# On_Axis_Encoder.net
KiCad netlist of a schematic drawn in EAGLE
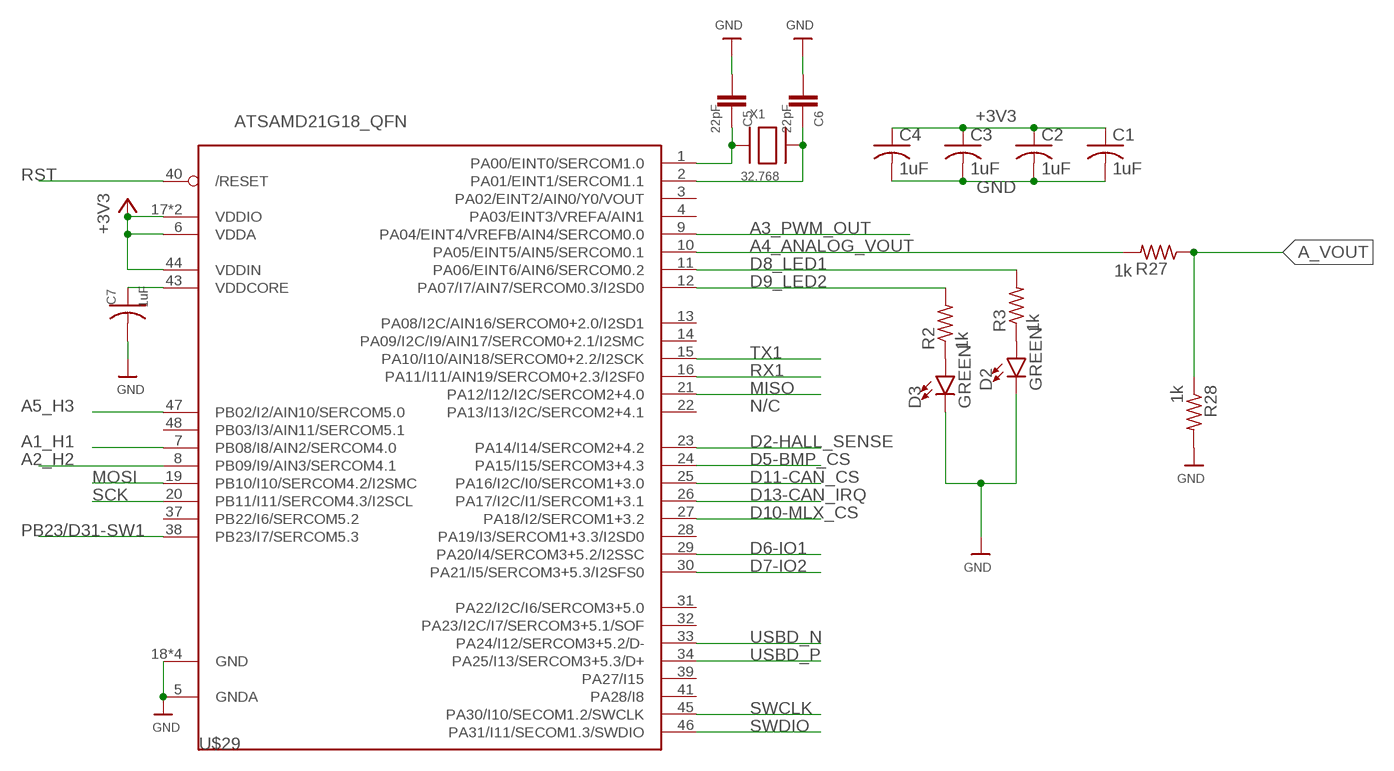
[diagram p0: schematic, sheet 1]
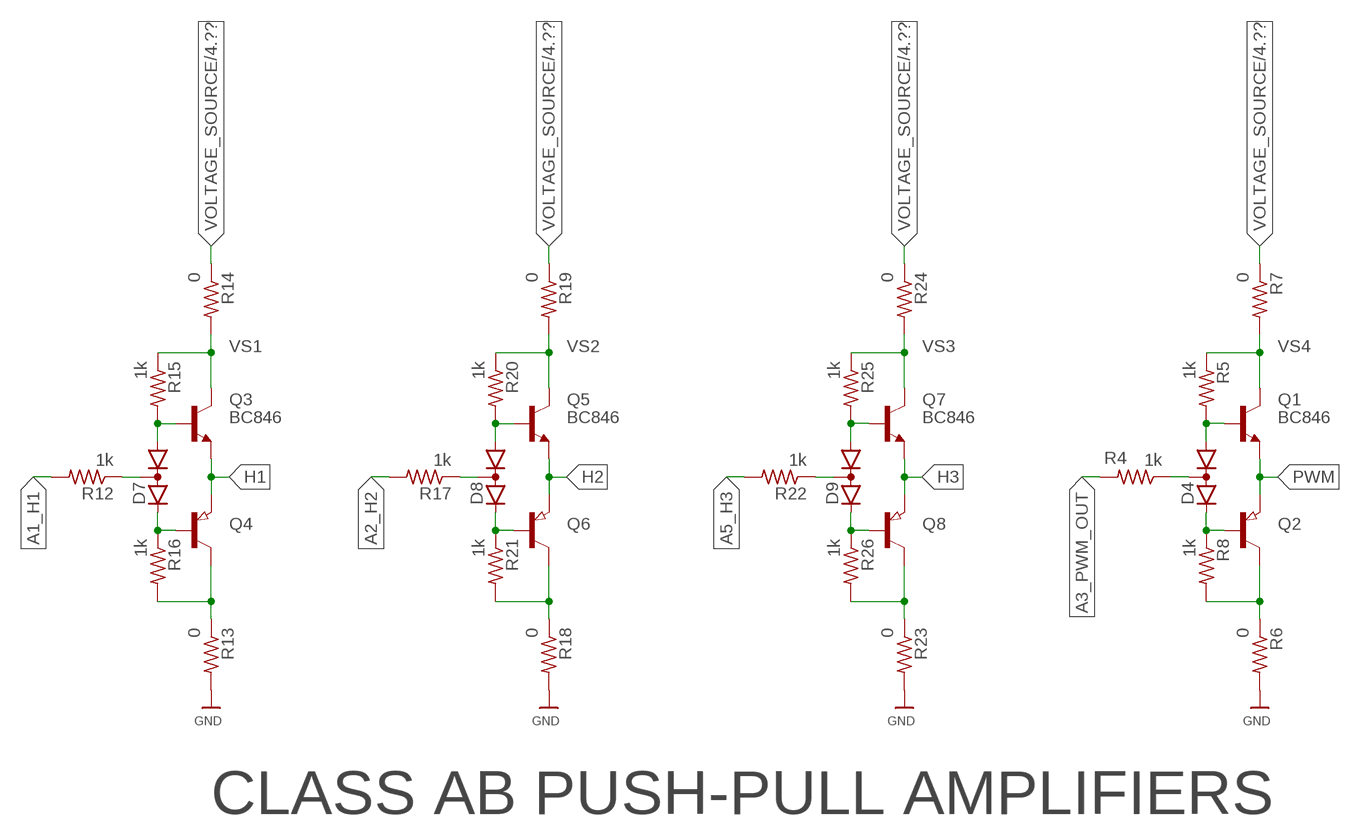
[diagram p1: schematic, sheet 2]
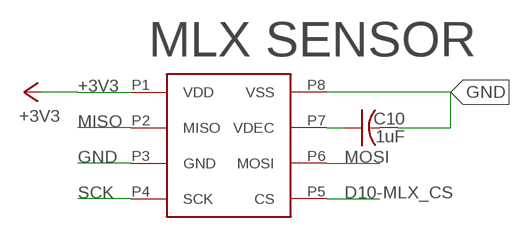
[diagram p2: schematic, sheet 3]
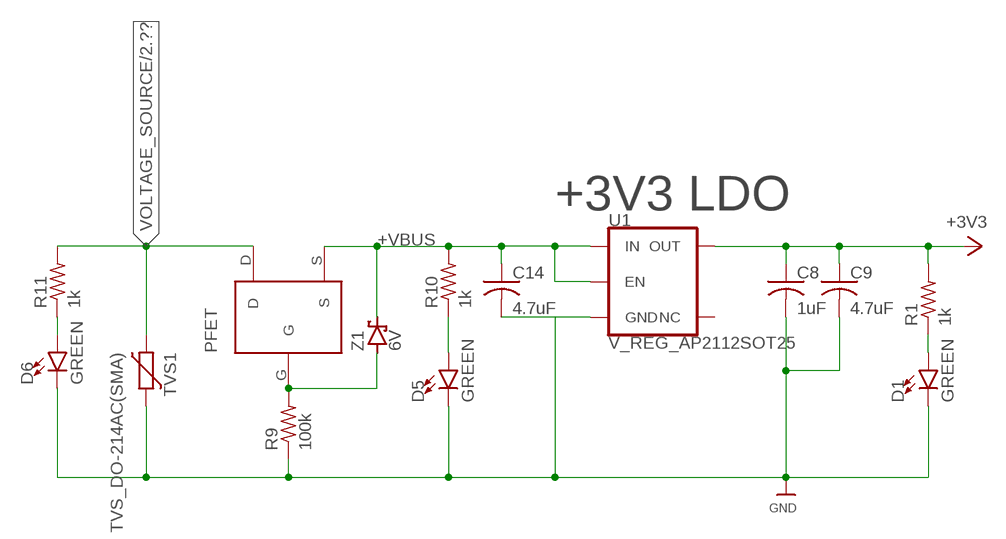
[diagram p3: schematic, sheet 4]
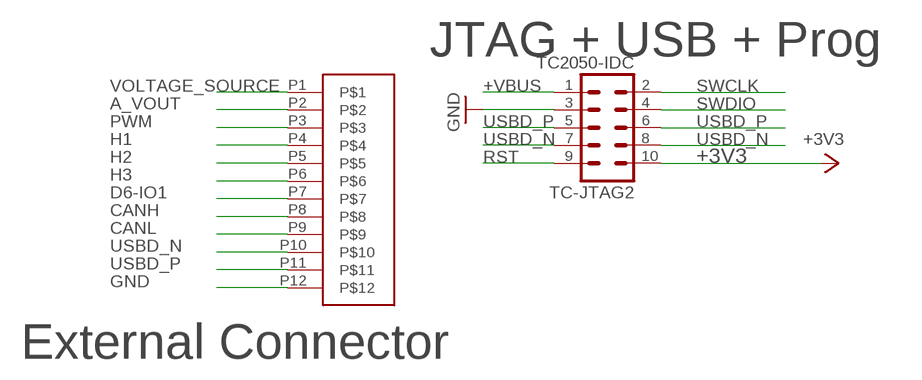
[diagram p4: schematic, sheet 5]
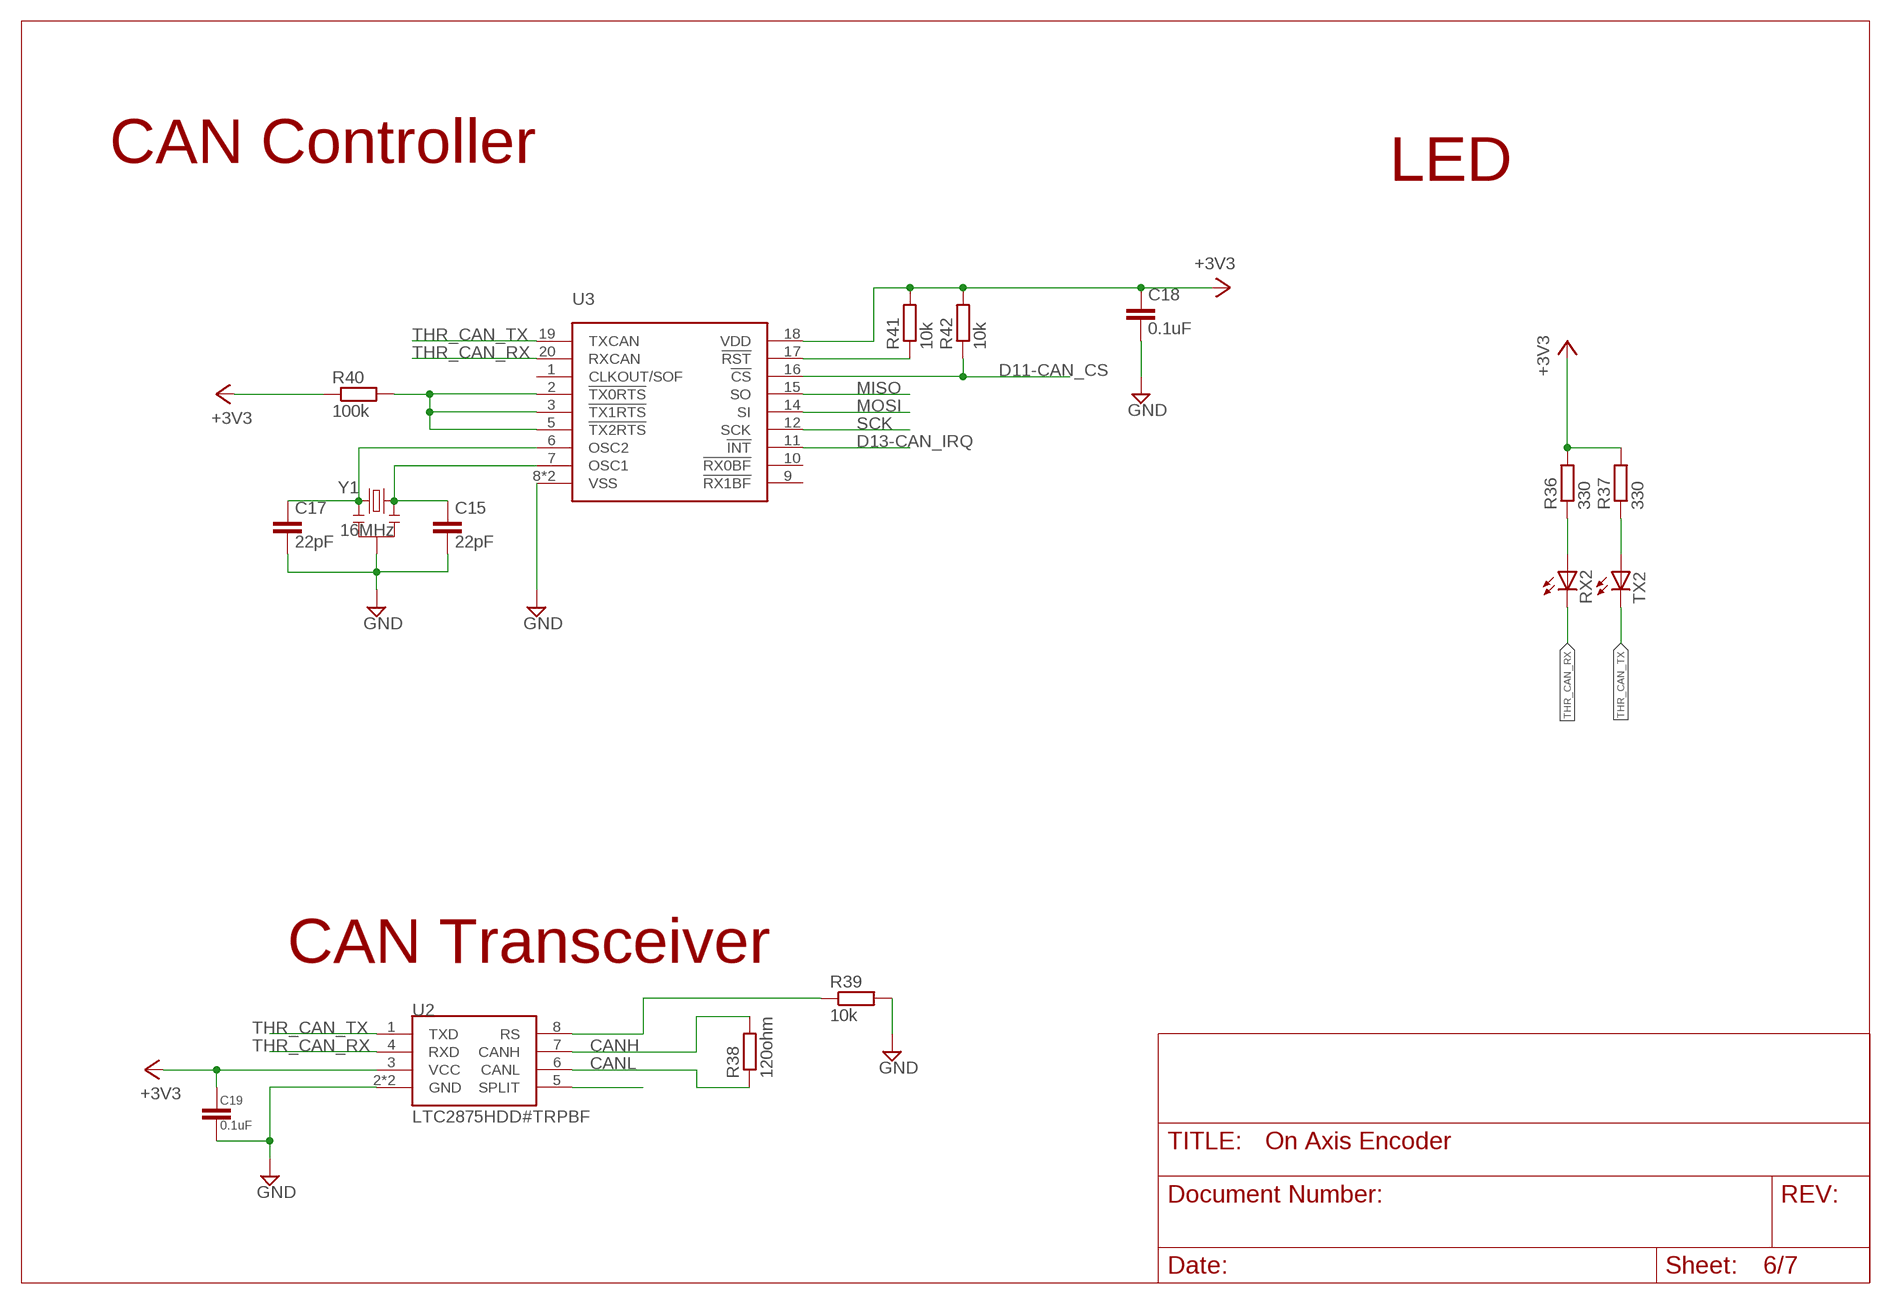
[diagram p5: schematic, sheet 6]

(export (version "E")
  (design (tool "Eeschema 10.0.6"))
  (components
    (comp (ref "D4")
      (value "DIODE_AC-AC__")
      (footprint "eagle-import:SOT23C")
      (libsource (lib "eagle-import") (part "DIODE_AC-AC__"))
    )
    (comp (ref "D7")
      (value "DIODE_AC-AC__")
      (footprint "eagle-import:SOT23C")
      (libsource (lib "eagle-import") (part "DIODE_AC-AC__"))
    )
    (comp (ref "D8")
      (value "DIODE_AC-AC__")
      (footprint "eagle-import:SOT23C")
      (libsource (lib "eagle-import") (part "DIODE_AC-AC__"))
    )
    (comp (ref "D9")
      (value "DIODE_AC-AC__")
      (footprint "eagle-import:SOT23C")
      (libsource (lib "eagle-import") (part "DIODE_AC-AC__"))
    )
    (comp (ref "Q1")
      (value "BC846")
      (footprint "eagle-import:SOT23")
      (libsource (lib "eagle-import") (part "BC846"))
    )
    (comp (ref "Q2")
      (value "PNP-TRANSISTOR_SOT23")
      (footprint "eagle-import:SOT23")
      (libsource (lib "eagle-import") (part "PNP-TRANSISTOR_SOT23"))
    )
    (comp (ref "Q3")
      (value "BC846")
      (footprint "eagle-import:SOT23")
      (libsource (lib "eagle-import") (part "BC846"))
    )
    (comp (ref "Q4")
      (value "PNP-TRANSISTOR_SOT23")
      (footprint "eagle-import:SOT23")
      (libsource (lib "eagle-import") (part "PNP-TRANSISTOR_SOT23"))
    )
    (comp (ref "Q5")
      (value "BC846")
      (footprint "eagle-import:SOT23")
      (libsource (lib "eagle-import") (part "BC846"))
    )
    (comp (ref "Q6")
      (value "PNP-TRANSISTOR_SOT23")
      (footprint "eagle-import:SOT23")
      (libsource (lib "eagle-import") (part "PNP-TRANSISTOR_SOT23"))
    )
    (comp (ref "Q7")
      (value "BC846")
      (footprint "eagle-import:SOT23")
      (libsource (lib "eagle-import") (part "BC846"))
    )
    (comp (ref "Q8")
      (value "PNP-TRANSISTOR_SOT23")
      (footprint "eagle-import:SOT23")
      (libsource (lib "eagle-import") (part "PNP-TRANSISTOR_SOT23"))
    )
    (comp (ref "R4")
      (value "1k")
      (footprint "eagle-import:R0603")
      (libsource (lib "eagle-import") (part "R-US_R0603"))
    )
    (comp (ref "R5")
      (value "1k")
      (footprint "eagle-import:R0603")
      (libsource (lib "eagle-import") (part "R-US_R0603"))
    )
    (comp (ref "R6")
      (value "0")
      (footprint "eagle-import:R0603")
      (libsource (lib "eagle-import") (part "R-US_R0603"))
    )
    (comp (ref "R7")
      (value "0")
      (footprint "eagle-import:R0603")
      (libsource (lib "eagle-import") (part "R-US_R0603"))
    )
    (comp (ref "R8")
      (value "1k")
      (footprint "eagle-import:R0603")
      (libsource (lib "eagle-import") (part "R-US_R0603"))
    )
    (comp (ref "R12")
      (value "1k")
      (footprint "eagle-import:R0603")
      (libsource (lib "eagle-import") (part "R-US_R0603"))
    )
    (comp (ref "R13")
      (value "0")
      (footprint "eagle-import:R0603")
      (libsource (lib "eagle-import") (part "R-US_R0603"))
    )
    (comp (ref "R14")
      (value "0")
      (footprint "eagle-import:R0603")
      (libsource (lib "eagle-import") (part "R-US_R0603"))
    )
    (comp (ref "R15")
      (value "1k")
      (footprint "eagle-import:R0603")
      (libsource (lib "eagle-import") (part "R-US_R0603"))
    )
    (comp (ref "R16")
      (value "1k")
      (footprint "eagle-import:R0603")
      (libsource (lib "eagle-import") (part "R-US_R0603"))
    )
    (comp (ref "R17")
      (value "1k")
      (footprint "eagle-import:R0603")
      (libsource (lib "eagle-import") (part "R-US_R0603"))
    )
    (comp (ref "R18")
      (value "0")
      (footprint "eagle-import:R0603")
      (libsource (lib "eagle-import") (part "R-US_R0603"))
    )
    (comp (ref "R19")
      (value "0")
      (footprint "eagle-import:R0603")
      (libsource (lib "eagle-import") (part "R-US_R0603"))
    )
    (comp (ref "R20")
      (value "1k")
      (footprint "eagle-import:R0603")
      (libsource (lib "eagle-import") (part "R-US_R0603"))
    )
    (comp (ref "R21")
      (value "1k")
      (footprint "eagle-import:R0603")
      (libsource (lib "eagle-import") (part "R-US_R0603"))
    )
    (comp (ref "R22")
      (value "1k")
      (footprint "eagle-import:R0603")
      (libsource (lib "eagle-import") (part "R-US_R0603"))
    )
    (comp (ref "R23")
      (value "0")
      (footprint "eagle-import:R0603")
      (libsource (lib "eagle-import") (part "R-US_R0603"))
    )
    (comp (ref "R24")
      (value "0")
      (footprint "eagle-import:R0603")
      (libsource (lib "eagle-import") (part "R-US_R0603"))
    )
    (comp (ref "R25")
      (value "1k")
      (footprint "eagle-import:R0603")
      (libsource (lib "eagle-import") (part "R-US_R0603"))
    )
    (comp (ref "R26")
      (value "1k")
      (footprint "eagle-import:R0603")
      (libsource (lib "eagle-import") (part "R-US_R0603"))
    )
    (comp (ref "C10")
      (value "1uF")
      (footprint "eagle-import:C0603")
      (libsource (lib "eagle-import") (part "C-USC0603"))
    )
    (comp (ref "U$4")
      (value "MLX90363-SOIC8")
      (footprint "eagle-import:SOIC-8")
      (libsource (lib "eagle-import") (part "MLX90363-SOIC8"))
    )
    (comp (ref "C15")
      (value "22pF")
      (footprint "eagle-import:C-0603")
      (libsource (lib "eagle-import") (part "C0603"))
    )
    (comp (ref "C17")
      (value "22pF")
      (footprint "eagle-import:C-0603")
      (libsource (lib "eagle-import") (part "C0603"))
    )
    (comp (ref "C18")
      (value "0.1uF")
      (footprint "eagle-import:C-0603")
      (libsource (lib "eagle-import") (part "C0603"))
    )
    (comp (ref "C19")
      (value "0.1uF")
      (footprint "eagle-import:C-0603")
      (libsource (lib "eagle-import") (part "C0603"))
    )
    (comp (ref "R36")
      (value "330")
      (footprint "eagle-import:R-0603")
      (libsource (lib "eagle-import") (part "R0603"))
    )
    (comp (ref "R37")
      (value "330")
      (footprint "eagle-import:R-0603")
      (libsource (lib "eagle-import") (part "R0603"))
    )
    (comp (ref "R38")
      (value "120ohm")
      (footprint "eagle-import:R-0603")
      (libsource (lib "eagle-import") (part "R0603"))
    )
    (comp (ref "R39")
      (value "10k")
      (footprint "eagle-import:R-0603")
      (libsource (lib "eagle-import") (part "R0603"))
    )
    (comp (ref "R40")
      (value "100k")
      (footprint "eagle-import:R-0603")
      (libsource (lib "eagle-import") (part "R0603"))
    )
    (comp (ref "R41")
      (value "10k")
      (footprint "eagle-import:R-0603")
      (libsource (lib "eagle-import") (part "R0603"))
    )
    (comp (ref "R42")
      (value "10k")
      (footprint "eagle-import:R-0603")
      (libsource (lib "eagle-import") (part "R0603"))
    )
    (comp (ref "RX2")
      (value "LEDCHIPLED_0805")
      (footprint "eagle-import:CHIPLED_0805")
      (libsource (lib "eagle-import") (part "LEDCHIPLED_0805"))
    )
    (comp (ref "TX2")
      (value "LEDCHIPLED_0805")
      (footprint "eagle-import:CHIPLED_0805")
      (libsource (lib "eagle-import") (part "LEDCHIPLED_0805"))
    )
    (comp (ref "U2")
      (value "LTC2875HDD#TRPBF")
      (footprint "eagle-import:SON50P300X300X80-9T165X238N")
      (libsource (lib "eagle-import") (part "LTC2875-8-DFN"))
    )
    (comp (ref "U3")
      (value "MCP2515-E/ML")
      (footprint "eagle-import:QFN50P400X400X100-21T270N")
      (libsource (lib "eagle-import") (part "MCP2515QFN-20"))
    )
    (comp (ref "Y1")
      (value "16MHz")
      (footprint "eagle-import:RESONATOR-SMD")
      (libsource (lib "eagle-import") (part "RESONATORSMD"))
    )
    (comp (ref "C1")
      (value "1uF")
      (footprint "eagle-import:C0603")
      (libsource (lib "eagle-import") (part "C-USC0603"))
    )
    (comp (ref "C2")
      (value "1uF")
      (footprint "eagle-import:C0603")
      (libsource (lib "eagle-import") (part "C-USC0603"))
    )
    (comp (ref "C3")
      (value "1uF")
      (footprint "eagle-import:C0603")
      (libsource (lib "eagle-import") (part "C-USC0603"))
    )
    (comp (ref "C4")
      (value "1uF")
      (footprint "eagle-import:C0603")
      (libsource (lib "eagle-import") (part "C-USC0603"))
    )
    (comp (ref "C5")
      (value "22pF")
      (footprint "eagle-import:C-0402")
      (libsource (lib "eagle-import") (part "C0402"))
    )
    (comp (ref "C6")
      (value "22pF")
      (footprint "eagle-import:C-0402")
      (libsource (lib "eagle-import") (part "C0402"))
    )
    (comp (ref "C7")
      (value "1uF")
      (footprint "eagle-import:C0603")
      (libsource (lib "eagle-import") (part "C-USC0603"))
    )
    (comp (ref "D2")
      (value "GREEN")
      (footprint "eagle-import:LED-0603")
      (libsource (lib "eagle-import") (part "LED-RED0603"))
    )
    (comp (ref "D3")
      (value "GREEN")
      (footprint "eagle-import:LED-0603")
      (libsource (lib "eagle-import") (part "LED-RED0603"))
    )
    (comp (ref "R2")
      (value "1k")
      (footprint "eagle-import:R0603")
      (libsource (lib "eagle-import") (part "R-US_R0603"))
    )
    (comp (ref "R3")
      (value "1k")
      (footprint "eagle-import:R0603")
      (libsource (lib "eagle-import") (part "R-US_R0603"))
    )
    (comp (ref "R27")
      (value "1k")
      (footprint "eagle-import:R0603")
      (libsource (lib "eagle-import") (part "R-US_R0603"))
    )
    (comp (ref "R28")
      (value "1k")
      (footprint "eagle-import:R0603")
      (libsource (lib "eagle-import") (part "R-US_R0603"))
    )
    (comp (ref "U$29")
      (value "ATSAMD21G18_QFN")
      (footprint "eagle-import:MICROBUILDER_TQFN48_7MM")
      (libsource (lib "eagle-import") (part "ATSAMD21J_QFN"))
    )
    (comp (ref "X1")
      (value "32.768")
      (footprint "eagle-import:XTAL3215")
      (libsource (lib "eagle-import") (part "XTAL-3.2X1.5"))
    )
    (comp (ref "TC-JTAG2")
      (value "TC2050-IDC")
      (footprint "eagle-import:TC2050-IDC")
      (libsource (lib "eagle-import") (part "TC2050-IDC"))
    )
    (comp (ref "U$9")
      (value "BM12B-ZESS-TBT")
      (footprint "eagle-import:JST-BM12B-ZESS-TBT")
      (libsource (lib "eagle-import") (part "BM12B-ZESS-TBT"))
    )
    (comp (ref "C8")
      (value "1uF")
      (footprint "eagle-import:C0603")
      (libsource (lib "eagle-import") (part "C-USC0603"))
    )
    (comp (ref "C9")
      (value "4.7uF")
      (footprint "eagle-import:C0603")
      (libsource (lib "eagle-import") (part "C-USC0603"))
    )
    (comp (ref "C14")
      (value "4.7uF")
      (footprint "eagle-import:C0603")
      (libsource (lib "eagle-import") (part "C-USC0603"))
    )
    (comp (ref "D1")
      (value "GREEN")
      (footprint "eagle-import:LED-0603")
      (libsource (lib "eagle-import") (part "LED-RED0603"))
    )
    (comp (ref "D5")
      (value "GREEN")
      (footprint "eagle-import:LED-0603")
      (libsource (lib "eagle-import") (part "LED-RED0603"))
    )
    (comp (ref "D6")
      (value "GREEN")
      (footprint "eagle-import:LED-0603")
      (libsource (lib "eagle-import") (part "LED-RED0603"))
    )
    (comp (ref "PFET1")
      (value "PFET")
      (footprint "eagle-import:SOT323-3_NFET")
      (libsource (lib "eagle-import") (part "NFET"))
    )
    (comp (ref "R1")
      (value "1k")
      (footprint "eagle-import:R0603")
      (libsource (lib "eagle-import") (part "R-US_R0603"))
    )
    (comp (ref "R9")
      (value "100k")
      (footprint "eagle-import:R0603")
      (libsource (lib "eagle-import") (part "R-US_R0603"))
    )
    (comp (ref "R10")
      (value "1k")
      (footprint "eagle-import:R0603")
      (libsource (lib "eagle-import") (part "R-US_R0603"))
    )
    (comp (ref "R11")
      (value "1k")
      (footprint "eagle-import:R0603")
      (libsource (lib "eagle-import") (part "R-US_R0603"))
    )
    (comp (ref "TVS1")
      (value "TVS_DO-214AC(SMA)")
      (footprint "eagle-import:DIOM5226X290N")
      (libsource (lib "eagle-import") (part "TVSDO-214AC(SMA)_"))
    )
    (comp (ref "U1")
      (value "V_REG_AP2112SOT25")
      (footprint "eagle-import:SOT95P285X140-5N")
      (libsource (lib "eagle-import") (part "V_REG_AP2112SOT25"))
    )
    (comp (ref "Z1")
      (value "6V")
      (footprint "eagle-import:SOT23")
      (libsource (lib "eagle-import") (part "BAS40"))
    )
  )
  (nets
    (net (code "1") (name "+3V3") (class "Default")
      (node (ref "C1") (pin "1") (pinfunction "1_1") (pintype "passive"))
      (node (ref "C18") (pin "P$1") (pinfunction "1_P$1") (pintype "passive"))
      (node (ref "C19") (pin "P$1") (pinfunction "1_P$1") (pintype "passive"))
      (node (ref "C2") (pin "1") (pinfunction "1_1") (pintype "passive"))
      (node (ref "C3") (pin "1") (pinfunction "1_1") (pintype "passive"))
      (node (ref "C4") (pin "1") (pinfunction "1_1") (pintype "passive"))
      (node (ref "C8") (pin "1") (pinfunction "1_1") (pintype "passive"))
      (node (ref "C9") (pin "1") (pinfunction "1_1") (pintype "passive"))
      (node (ref "R1") (pin "2") (pinfunction "2_2") (pintype "passive"))
      (node (ref "R36") (pin "P$2") (pinfunction "2_P$2") (pintype "passive"))
      (node (ref "R37") (pin "P$2") (pinfunction "2_P$2") (pintype "passive"))
      (node (ref "R40") (pin "P$1") (pinfunction "1_P$1") (pintype "passive"))
      (node (ref "R41") (pin "P$2") (pinfunction "2_P$2") (pintype "passive"))
      (node (ref "R42") (pin "P$2") (pinfunction "2_P$2") (pintype "passive"))
      (node (ref "TC-JTAG2") (pin "10") (pinfunction "10_10") (pintype "passive"))
      (node (ref "U$29") (pin "17") (pinfunction "VDDIO_17") (pintype "power_in"))
      (node (ref "U$29") (pin "36") (pinfunction "VDDIO_36") (pintype "power_in"))
      (node (ref "U$29") (pin "44") (pinfunction "VDDIN_44") (pintype "power_in"))
      (node (ref "U$29") (pin "6") (pinfunction "VDDA_6") (pintype "power_in"))
      (node (ref "U$4") (pin "P1") (pinfunction "VDD_P1") (pintype "bidirectional"))
      (node (ref "U1") (pin "5") (pinfunction "OUT_5") (pintype "passive"))
      (node (ref "U2") (pin "3") (pinfunction "VCC_3") (pintype "bidirectional"))
      (node (ref "U3") (pin "18") (pinfunction "VDD_18") (pintype "bidirectional"))
    )
    (net (code "2") (name "+VBUS") (class "Default")
      (node (ref "C14") (pin "1") (pinfunction "1_1") (pintype "passive"))
      (node (ref "PFET1") (pin "S") (pinfunction "S_S") (pintype "bidirectional"))
      (node (ref "R10") (pin "2") (pinfunction "2_2") (pintype "passive"))
      (node (ref "TC-JTAG2") (pin "1") (pinfunction "1_1") (pintype "passive"))
      (node (ref "U1") (pin "1") (pinfunction "IN_1") (pintype "input"))
      (node (ref "U1") (pin "3") (pinfunction "EN_3") (pintype "input"))
      (node (ref "Z1") (pin "3") (pinfunction "C_3") (pintype "passive"))
    )
    (net (code "3") (name "A1_H1") (class "Default")
      (node (ref "R12") (pin "2") (pinfunction "2_2") (pintype "passive"))
      (node (ref "U$29") (pin "7") (pinfunction "PB08/I8/AIN2/SERCOM4.0_7") (pintype "bidirectional"))
    )
    (net (code "4") (name "A2_H2") (class "Default")
      (node (ref "R17") (pin "2") (pinfunction "2_2") (pintype "passive"))
      (node (ref "U$29") (pin "8") (pinfunction "PB09/I9/AIN3/SERCOM4.1_8") (pintype "bidirectional"))
    )
    (net (code "5") (name "A3_PWM_OUT") (class "Default")
      (node (ref "R4") (pin "2") (pinfunction "2_2") (pintype "passive"))
      (node (ref "U$29") (pin "9") (pinfunction "PA04/EINT4/VREFB/AIN4/SERCOM0.0_9") (pintype "bidirectional"))
    )
    (net (code "6") (name "A4_ANALOG_VOUT") (class "Default")
      (node (ref "R27") (pin "2") (pinfunction "2_2") (pintype "passive"))
      (node (ref "U$29") (pin "10") (pinfunction "PA05/EINT5/AIN5/SERCOM0.1_10") (pintype "bidirectional"))
    )
    (net (code "7") (name "A5_H3") (class "Default")
      (node (ref "R22") (pin "2") (pinfunction "2_2") (pintype "passive"))
      (node (ref "U$29") (pin "47") (pinfunction "PB02/I2/AIN10/SERCOM5.0_47") (pintype "bidirectional"))
    )
    (net (code "8") (name "A_VOUT") (class "Default")
      (node (ref "R27") (pin "1") (pinfunction "1_1") (pintype "passive"))
      (node (ref "R28") (pin "1") (pinfunction "1_1") (pintype "passive"))
      (node (ref "U$9") (pin "P2") (pinfunction "P$2_P2") (pintype "bidirectional"))
    )
    (net (code "9") (name "CANH") (class "Default")
      (node (ref "R38") (pin "P$2") (pinfunction "2_P$2") (pintype "passive"))
      (node (ref "U$9") (pin "P8") (pinfunction "P$8_P8") (pintype "bidirectional"))
      (node (ref "U2") (pin "7") (pinfunction "CANH_7") (pintype "bidirectional"))
    )
    (net (code "10") (name "CANL") (class "Default")
      (node (ref "R38") (pin "P$1") (pinfunction "1_P$1") (pintype "passive"))
      (node (ref "U$9") (pin "P9") (pinfunction "P$9_P9") (pintype "bidirectional"))
      (node (ref "U2") (pin "6") (pinfunction "CANL_6") (pintype "bidirectional"))
    )
    (net (code "11") (name "D2-HALL_SENSE") (class "Default")
      (node (ref "U$29") (pin "23") (pinfunction "PA14/I14/SERCOM2+4.2_23") (pintype "bidirectional"))
    )
    (net (code "12") (name "D5-BMP_CS") (class "Default")
      (node (ref "U$29") (pin "24") (pinfunction "PA15/I15/SERCOM3+4.3_24") (pintype "bidirectional"))
    )
    (net (code "13") (name "D6-IO1") (class "Default")
      (node (ref "U$29") (pin "29") (pinfunction "PA20/I4/SERCOM3+5.2/I2SSC_29") (pintype "bidirectional"))
      (node (ref "U$9") (pin "P7") (pinfunction "P$7_P7") (pintype "bidirectional"))
    )
    (net (code "14") (name "D7-IO2") (class "Default")
      (node (ref "U$29") (pin "30") (pinfunction "PA21/I5/SERCOM3+5.3/I2SFS0_30") (pintype "bidirectional"))
    )
    (net (code "15") (name "D8_LED1") (class "Default")
      (node (ref "R3") (pin "2") (pinfunction "2_2") (pintype "passive"))
      (node (ref "U$29") (pin "11") (pinfunction "PA06/EINT6/AIN6/SERCOM0.2_11") (pintype "bidirectional"))
    )
    (net (code "16") (name "D9_LED2") (class "Default")
      (node (ref "R2") (pin "2") (pinfunction "2_2") (pintype "passive"))
      (node (ref "U$29") (pin "12") (pinfunction "PA07/I7/AIN7/SERCOM0.3/I2SD0_12") (pintype "bidirectional"))
    )
    (net (code "17") (name "D10-MLX_CS") (class "Default")
      (node (ref "U$29") (pin "27") (pinfunction "PA18/I2/SERCOM1+3.2_27") (pintype "bidirectional"))
      (node (ref "U$4") (pin "P5") (pinfunction "CS_P5") (pintype "bidirectional"))
    )
    (net (code "18") (name "D11-CAN_CS") (class "Default")
      (node (ref "R42") (pin "P$1") (pinfunction "1_P$1") (pintype "passive"))
      (node (ref "U$29") (pin "25") (pinfunction "PA16/I2C/I0/SERCOM1+3.0_25") (pintype "bidirectional"))
      (node (ref "U3") (pin "16") (pinfunction "~{CS}_16") (pintype "bidirectional"))
    )
    (net (code "19") (name "D13-CAN_IRQ") (class "Default")
      (node (ref "U$29") (pin "26") (pinfunction "PA17/I2C/I1/SERCOM1+3.1_26") (pintype "bidirectional"))
      (node (ref "U3") (pin "11") (pinfunction "~{INT}_11") (pintype "bidirectional"))
    )
    (net (code "20") (name "GND") (class "Default")
      (node (ref "C1") (pin "2") (pinfunction "2_2") (pintype "passive"))
      (node (ref "C10") (pin "2") (pinfunction "2_2") (pintype "passive"))
      (node (ref "C14") (pin "2") (pinfunction "2_2") (pintype "passive"))
      (node (ref "C15") (pin "P$2") (pinfunction "2_P$2") (pintype "passive"))
      (node (ref "C17") (pin "P$2") (pinfunction "2_P$2") (pintype "passive"))
      (node (ref "C18") (pin "P$2") (pinfunction "2_P$2") (pintype "passive"))
      (node (ref "C19") (pin "P$2") (pinfunction "2_P$2") (pintype "passive"))
      (node (ref "C2") (pin "2") (pinfunction "2_2") (pintype "passive"))
      (node (ref "C3") (pin "2") (pinfunction "2_2") (pintype "passive"))
      (node (ref "C4") (pin "2") (pinfunction "2_2") (pintype "passive"))
      (node (ref "C5") (pin "P$2") (pinfunction "2_P$2") (pintype "passive"))
      (node (ref "C6") (pin "P$2") (pinfunction "2_P$2") (pintype "passive"))
      (node (ref "C7") (pin "2") (pinfunction "2_2") (pintype "passive"))
      (node (ref "C8") (pin "2") (pinfunction "2_2") (pintype "passive"))
      (node (ref "C9") (pin "2") (pinfunction "2_2") (pintype "passive"))
      (node (ref "D1") (pin "C") (pinfunction "C_C") (pintype "passive"))
      (node (ref "D2") (pin "C") (pinfunction "C_C") (pintype "passive"))
      (node (ref "D3") (pin "C") (pinfunction "C_C") (pintype "passive"))
      (node (ref "D5") (pin "C") (pinfunction "C_C") (pintype "passive"))
      (node (ref "D6") (pin "C") (pinfunction "C_C") (pintype "passive"))
      (node (ref "R13") (pin "2") (pinfunction "2_2") (pintype "passive"))
      (node (ref "R18") (pin "2") (pinfunction "2_2") (pintype "passive"))
      (node (ref "R23") (pin "2") (pinfunction "2_2") (pintype "passive"))
      (node (ref "R28") (pin "2") (pinfunction "2_2") (pintype "passive"))
      (node (ref "R39") (pin "P$2") (pinfunction "2_P$2") (pintype "passive"))
      (node (ref "R6") (pin "2") (pinfunction "2_2") (pintype "passive"))
      (node (ref "R9") (pin "1") (pinfunction "1_1") (pintype "passive"))
      (node (ref "TC-JTAG2") (pin "3") (pinfunction "3_3") (pintype "passive"))
      (node (ref "TVS1") (pin "2") (pinfunction "2_2") (pintype "passive"))
      (node (ref "U$29") (pin "18") (pinfunction "GND_18") (pintype "power_in"))
      (node (ref "U$29") (pin "35") (pinfunction "GND_35") (pintype "power_in"))
      (node (ref "U$29") (pin "42") (pinfunction "GND_42") (pintype "power_in"))
      (node (ref "U$29") (pin "5") (pinfunction "GNDA_5") (pintype "power_in"))
      (node (ref "U$29") (pin "THERMAL") (pinfunction "GND_THERMAL") (pintype "power_in"))
      (node (ref "U$4") (pin "P3") (pinfunction "GND_P3") (pintype "bidirectional"))
      (node (ref "U$4") (pin "P8") (pinfunction "VSS_P8") (pintype "bidirectional"))
      (node (ref "U$9") (pin "P12") (pinfunction "P$12_P12") (pintype "bidirectional"))
      (node (ref "U1") (pin "2") (pinfunction "GND_2") (pintype "input"))
      (node (ref "U2") (pin "2") (pinfunction "GND_2") (pintype "bidirectional"))
      (node (ref "U2") (pin "9") (pinfunction "GND_9") (pintype "bidirectional"))
      (node (ref "U3") (pin "21") (pinfunction "VSS_21") (pintype "bidirectional"))
      (node (ref "U3") (pin "8") (pinfunction "VSS_8") (pintype "bidirectional"))
      (node (ref "Y1") (pin "2") (pinfunction "2_2") (pintype "passive"))
    )
    (net (code "21") (name "H1") (class "Default")
      (node (ref "Q3") (pin "2") (pinfunction "E_2") (pintype "passive"))
      (node (ref "Q4") (pin "2") (pinfunction "E_2") (pintype "passive"))
      (node (ref "U$9") (pin "P4") (pinfunction "P$4_P4") (pintype "bidirectional"))
    )
    (net (code "22") (name "H2") (class "Default")
      (node (ref "Q5") (pin "2") (pinfunction "E_2") (pintype "passive"))
      (node (ref "Q6") (pin "2") (pinfunction "E_2") (pintype "passive"))
      (node (ref "U$9") (pin "P5") (pinfunction "P$5_P5") (pintype "bidirectional"))
    )
    (net (code "23") (name "H3") (class "Default")
      (node (ref "Q7") (pin "2") (pinfunction "E_2") (pintype "passive"))
      (node (ref "Q8") (pin "2") (pinfunction "E_2") (pintype "passive"))
      (node (ref "U$9") (pin "P6") (pinfunction "P$6_P6") (pintype "bidirectional"))
    )
    (net (code "24") (name "MISO") (class "Default")
      (node (ref "U$29") (pin "21") (pinfunction "PA12/I12/I2C/SERCOM2+4.0_21") (pintype "bidirectional"))
      (node (ref "U$4") (pin "P2") (pinfunction "MISO_P2") (pintype "bidirectional"))
      (node (ref "U3") (pin "15") (pinfunction "SO_15") (pintype "bidirectional"))
    )
    (net (code "25") (name "MOSI") (class "Default")
      (node (ref "U$29") (pin "19") (pinfunction "PB10/I10/SERCOM4.2/I2SMC_19") (pintype "bidirectional"))
      (node (ref "U$4") (pin "P6") (pinfunction "MOSI_P6") (pintype "bidirectional"))
      (node (ref "U3") (pin "14") (pinfunction "SI_14") (pintype "bidirectional"))
    )
    (net (code "26") (name "Net-(C5-1)") (class "Default")
      (node (ref "C5") (pin "P$1") (pinfunction "1_P$1") (pintype "passive"))
      (node (ref "U$29") (pin "1") (pinfunction "PA00/EINT0/SERCOM1.0_1") (pintype "bidirectional"))
      (node (ref "X1") (pin "P$1") (pinfunction "P$1_P$1") (pintype "bidirectional"))
    )
    (net (code "27") (name "Net-(C6-1)") (class "Default")
      (node (ref "C6") (pin "P$1") (pinfunction "1_P$1") (pintype "passive"))
      (node (ref "U$29") (pin "2") (pinfunction "PA01/EINT1/SERCOM1.1_2") (pintype "bidirectional"))
      (node (ref "X1") (pin "P$2") (pinfunction "P$2_P$2") (pintype "bidirectional"))
    )
    (net (code "28") (name "Net-(C15-1)") (class "Default")
      (node (ref "C15") (pin "P$1") (pinfunction "1_P$1") (pintype "passive"))
      (node (ref "U3") (pin "7") (pinfunction "OSC1_7") (pintype "bidirectional"))
      (node (ref "Y1") (pin "1") (pinfunction "1_1") (pintype "passive"))
    )
    (net (code "29") (name "Net-(C17-1)") (class "Default")
      (node (ref "C17") (pin "P$1") (pinfunction "1_P$1") (pintype "passive"))
      (node (ref "U3") (pin "6") (pinfunction "OSC2_6") (pintype "bidirectional"))
      (node (ref "Y1") (pin "3") (pinfunction "3_3") (pintype "passive"))
    )
    (net (code "30") (name "Net-(D1-PadA)") (class "Default")
      (node (ref "D1") (pin "A") (pinfunction "A_A") (pintype "passive"))
      (node (ref "R1") (pin "1") (pinfunction "1_1") (pintype "passive"))
    )
    (net (code "31") (name "Net-(D2-PadA)") (class "Default")
      (node (ref "D2") (pin "A") (pinfunction "A_A") (pintype "passive"))
      (node (ref "R3") (pin "1") (pinfunction "1_1") (pintype "passive"))
    )
    (net (code "32") (name "Net-(D3-PadA)") (class "Default")
      (node (ref "D3") (pin "A") (pinfunction "A_A") (pintype "passive"))
      (node (ref "R2") (pin "1") (pinfunction "1_1") (pintype "passive"))
    )
    (net (code "33") (name "Net-(D4-A)") (class "Default")
      (node (ref "D4") (pin "2") (pinfunction "A_2") (pintype "passive"))
      (node (ref "Q1") (pin "1") (pinfunction "B_1") (pintype "passive"))
      (node (ref "R5") (pin "2") (pinfunction "2_2") (pintype "passive"))
    )
    (net (code "34") (name "Net-(D4-AK)") (class "Default")
      (node (ref "D4") (pin "3") (pinfunction "AK_3") (pintype "passive"))
      (node (ref "R4") (pin "1") (pinfunction "1_1") (pintype "passive"))
    )
    (net (code "35") (name "Net-(D4-K)") (class "Default")
      (node (ref "D4") (pin "1") (pinfunction "K_1") (pintype "passive"))
      (node (ref "Q2") (pin "1") (pinfunction "B_1") (pintype "passive"))
      (node (ref "R8") (pin "1") (pinfunction "1_1") (pintype "passive"))
    )
    (net (code "36") (name "Net-(D5-PadA)") (class "Default")
      (node (ref "D5") (pin "A") (pinfunction "A_A") (pintype "passive"))
      (node (ref "R10") (pin "1") (pinfunction "1_1") (pintype "passive"))
    )
    (net (code "37") (name "Net-(D6-PadA)") (class "Default")
      (node (ref "D6") (pin "A") (pinfunction "A_A") (pintype "passive"))
      (node (ref "R11") (pin "1") (pinfunction "1_1") (pintype "passive"))
    )
    (net (code "38") (name "Net-(D7-A)") (class "Default")
      (node (ref "D7") (pin "2") (pinfunction "A_2") (pintype "passive"))
      (node (ref "Q3") (pin "1") (pinfunction "B_1") (pintype "passive"))
      (node (ref "R15") (pin "2") (pinfunction "2_2") (pintype "passive"))
    )
    (net (code "39") (name "Net-(D7-AK)") (class "Default")
      (node (ref "D7") (pin "3") (pinfunction "AK_3") (pintype "passive"))
      (node (ref "R12") (pin "1") (pinfunction "1_1") (pintype "passive"))
    )
    (net (code "40") (name "Net-(D7-K)") (class "Default")
      (node (ref "D7") (pin "1") (pinfunction "K_1") (pintype "passive"))
      (node (ref "Q4") (pin "1") (pinfunction "B_1") (pintype "passive"))
      (node (ref "R16") (pin "1") (pinfunction "1_1") (pintype "passive"))
    )
    (net (code "41") (name "Net-(D8-A)") (class "Default")
      (node (ref "D8") (pin "2") (pinfunction "A_2") (pintype "passive"))
      (node (ref "Q5") (pin "1") (pinfunction "B_1") (pintype "passive"))
      (node (ref "R20") (pin "2") (pinfunction "2_2") (pintype "passive"))
    )
    (net (code "42") (name "Net-(D8-AK)") (class "Default")
      (node (ref "D8") (pin "3") (pinfunction "AK_3") (pintype "passive"))
      (node (ref "R17") (pin "1") (pinfunction "1_1") (pintype "passive"))
    )
    (net (code "43") (name "Net-(D8-K)") (class "Default")
      (node (ref "D8") (pin "1") (pinfunction "K_1") (pintype "passive"))
      (node (ref "Q6") (pin "1") (pinfunction "B_1") (pintype "passive"))
      (node (ref "R21") (pin "1") (pinfunction "1_1") (pintype "passive"))
    )
    (net (code "44") (name "Net-(D9-A)") (class "Default")
      (node (ref "D9") (pin "2") (pinfunction "A_2") (pintype "passive"))
      (node (ref "Q7") (pin "1") (pinfunction "B_1") (pintype "passive"))
      (node (ref "R25") (pin "2") (pinfunction "2_2") (pintype "passive"))
    )
    (net (code "45") (name "Net-(D9-AK)") (class "Default")
      (node (ref "D9") (pin "3") (pinfunction "AK_3") (pintype "passive"))
      (node (ref "R22") (pin "1") (pinfunction "1_1") (pintype "passive"))
    )
    (net (code "46") (name "Net-(D9-K)") (class "Default")
      (node (ref "D9") (pin "1") (pinfunction "K_1") (pintype "passive"))
      (node (ref "Q8") (pin "1") (pinfunction "B_1") (pintype "passive"))
      (node (ref "R26") (pin "1") (pinfunction "1_1") (pintype "passive"))
    )
    (net (code "47") (name "Net-(Q2-C)") (class "Default")
      (node (ref "Q2") (pin "3") (pinfunction "C_3") (pintype "passive"))
      (node (ref "R6") (pin "1") (pinfunction "1_1") (pintype "passive"))
      (node (ref "R8") (pin "2") (pinfunction "2_2") (pintype "passive"))
    )
    (net (code "48") (name "Net-(Q4-C)") (class "Default")
      (node (ref "Q4") (pin "3") (pinfunction "C_3") (pintype "passive"))
      (node (ref "R13") (pin "1") (pinfunction "1_1") (pintype "passive"))
      (node (ref "R16") (pin "2") (pinfunction "2_2") (pintype "passive"))
    )
    (net (code "49") (name "Net-(Q6-C)") (class "Default")
      (node (ref "Q6") (pin "3") (pinfunction "C_3") (pintype "passive"))
      (node (ref "R18") (pin "1") (pinfunction "1_1") (pintype "passive"))
      (node (ref "R21") (pin "2") (pinfunction "2_2") (pintype "passive"))
    )
    (net (code "50") (name "Net-(Q8-C)") (class "Default")
      (node (ref "Q8") (pin "3") (pinfunction "C_3") (pintype "passive"))
      (node (ref "R23") (pin "1") (pinfunction "1_1") (pintype "passive"))
      (node (ref "R26") (pin "2") (pinfunction "2_2") (pintype "passive"))
    )
    (net (code "51") (name "Net-(R36-1)") (class "Default")
      (node (ref "R36") (pin "P$1") (pinfunction "1_P$1") (pintype "passive"))
      (node (ref "RX2") (pin "A") (pinfunction "A_A") (pintype "passive"))
    )
    (net (code "52") (name "Net-(R37-1)") (class "Default")
      (node (ref "R37") (pin "P$1") (pinfunction "1_P$1") (pintype "passive"))
      (node (ref "TX2") (pin "A") (pinfunction "A_A") (pintype "passive"))
    )
    (net (code "53") (name "Net-(R39-1)") (class "Default")
      (node (ref "R39") (pin "P$1") (pinfunction "1_P$1") (pintype "passive"))
      (node (ref "U2") (pin "8") (pinfunction "RS_8") (pintype "bidirectional"))
    )
    (net (code "54") (name "Net-(R40-2)") (class "Default")
      (node (ref "R40") (pin "P$2") (pinfunction "2_P$2") (pintype "passive"))
      (node (ref "U3") (pin "2") (pinfunction "~{TX0RTS}_2") (pintype "bidirectional"))
      (node (ref "U3") (pin "3") (pinfunction "~{TX1RTS}_3") (pintype "bidirectional"))
      (node (ref "U3") (pin "5") (pinfunction "~{TX2RTS}_5") (pintype "bidirectional"))
    )
    (net (code "55") (name "Net-(R41-1)") (class "Default")
      (node (ref "R41") (pin "P$1") (pinfunction "1_P$1") (pintype "passive"))
      (node (ref "U3") (pin "17") (pinfunction "~{RST}_17") (pintype "bidirectional"))
    )
    (net (code "56") (name "Net-(U$4-VDEC)") (class "Default")
      (node (ref "C10") (pin "1") (pinfunction "1_1") (pintype "passive"))
      (node (ref "U$4") (pin "P7") (pinfunction "VDEC_P7") (pintype "bidirectional"))
    )
    (net (code "57") (name "Net-(U$29-VDDCORE)") (class "Default")
      (node (ref "C7") (pin "1") (pinfunction "1_1") (pintype "passive"))
      (node (ref "U$29") (pin "43") (pinfunction "VDDCORE_43") (pintype "power_in"))
    )
    (net (code "58") (name "Net-(Z1-A)") (class "Default")
      (node (ref "PFET1") (pin "G") (pinfunction "G_G") (pintype "bidirectional"))
      (node (ref "R9") (pin "2") (pinfunction "2_2") (pintype "passive"))
      (node (ref "Z1") (pin "1") (pinfunction "A_1") (pintype "passive"))
    )
    (net (code "59") (name "PB23{slash}D31-SW1") (class "Default")
      (node (ref "U$29") (pin "38") (pinfunction "PB23/I7/SERCOM5.3_38") (pintype "bidirectional"))
    )
    (net (code "60") (name "PWM") (class "Default")
      (node (ref "Q1") (pin "2") (pinfunction "E_2") (pintype "passive"))
      (node (ref "Q2") (pin "2") (pinfunction "E_2") (pintype "passive"))
      (node (ref "U$9") (pin "P3") (pinfunction "P$3_P3") (pintype "bidirectional"))
    )
    (net (code "61") (name "RST") (class "Default")
      (node (ref "TC-JTAG2") (pin "9") (pinfunction "9_9") (pintype "passive"))
      (node (ref "U$29") (pin "40") (pinfunction "/RESET_40") (pintype "bidirectional"))
    )
    (net (code "62") (name "RX1") (class "Default")
      (node (ref "U$29") (pin "16") (pinfunction "PA11/I11/AIN19/SERCOM0+2.3/I2SF0_16") (pintype "bidirectional"))
    )
    (net (code "63") (name "SCK") (class "Default")
      (node (ref "U$29") (pin "20") (pinfunction "PB11/I11/SERCOM4.3/I2SCL_20") (pintype "bidirectional"))
      (node (ref "U$4") (pin "P4") (pinfunction "SCK_P4") (pintype "bidirectional"))
      (node (ref "U3") (pin "12") (pinfunction "SCK_12") (pintype "bidirectional"))
    )
    (net (code "64") (name "SWCLK") (class "Default")
      (node (ref "TC-JTAG2") (pin "2") (pinfunction "2_2") (pintype "passive"))
      (node (ref "U$29") (pin "45") (pinfunction "PA30/I10/SECOM1.2/SWCLK_45") (pintype "bidirectional"))
    )
    (net (code "65") (name "SWDIO") (class "Default")
      (node (ref "TC-JTAG2") (pin "4") (pinfunction "4_4") (pintype "passive"))
      (node (ref "U$29") (pin "46") (pinfunction "PA31/I11/SECOM1.3/SWDIO_46") (pintype "bidirectional"))
    )
    (net (code "66") (name "THR_CAN_RX") (class "Default")
      (node (ref "RX2") (pin "C") (pinfunction "C_C") (pintype "passive"))
      (node (ref "U2") (pin "4") (pinfunction "RXD_4") (pintype "bidirectional"))
      (node (ref "U3") (pin "20") (pinfunction "RXCAN_20") (pintype "bidirectional"))
    )
    (net (code "67") (name "THR_CAN_TX") (class "Default")
      (node (ref "TX2") (pin "C") (pinfunction "C_C") (pintype "passive"))
      (node (ref "U2") (pin "1") (pinfunction "TXD_1") (pintype "bidirectional"))
      (node (ref "U3") (pin "19") (pinfunction "TXCAN_19") (pintype "bidirectional"))
    )
    (net (code "68") (name "TX1") (class "Default")
      (node (ref "U$29") (pin "15") (pinfunction "PA10/I10/AIN18/SERCOM0+2.2/I2SCK_15") (pintype "bidirectional"))
    )
    (net (code "69") (name "USBD_N") (class "Default")
      (node (ref "TC-JTAG2") (pin "7") (pinfunction "7_7") (pintype "passive"))
      (node (ref "TC-JTAG2") (pin "8") (pinfunction "8_8") (pintype "passive"))
      (node (ref "U$29") (pin "33") (pinfunction "PA24/I12/SERCOM3+5.2/D-_33") (pintype "bidirectional"))
      (node (ref "U$9") (pin "P10") (pinfunction "P$10_P10") (pintype "bidirectional"))
    )
    (net (code "70") (name "USBD_P") (class "Default")
      (node (ref "TC-JTAG2") (pin "5") (pinfunction "5_5") (pintype "passive"))
      (node (ref "TC-JTAG2") (pin "6") (pinfunction "6_6") (pintype "passive"))
      (node (ref "U$29") (pin "34") (pinfunction "PA25/I13/SERCOM3+5.3/D+_34") (pintype "bidirectional"))
      (node (ref "U$9") (pin "P11") (pinfunction "P$11_P11") (pintype "bidirectional"))
    )
    (net (code "71") (name "VOLTAGE_SOURCE") (class "Default")
      (node (ref "PFET1") (pin "D") (pinfunction "D_D") (pintype "bidirectional"))
      (node (ref "R11") (pin "2") (pinfunction "2_2") (pintype "passive"))
      (node (ref "R14") (pin "1") (pinfunction "1_1") (pintype "passive"))
      (node (ref "R19") (pin "1") (pinfunction "1_1") (pintype "passive"))
      (node (ref "R24") (pin "1") (pinfunction "1_1") (pintype "passive"))
      (node (ref "R7") (pin "1") (pinfunction "1_1") (pintype "passive"))
      (node (ref "TVS1") (pin "1") (pinfunction "1_1") (pintype "passive"))
      (node (ref "U$9") (pin "P1") (pinfunction "P$1_P1") (pintype "bidirectional"))
    )
    (net (code "72") (name "VS1") (class "Default")
      (node (ref "Q3") (pin "3") (pinfunction "C_3") (pintype "passive"))
      (node (ref "R14") (pin "2") (pinfunction "2_2") (pintype "passive"))
      (node (ref "R15") (pin "1") (pinfunction "1_1") (pintype "passive"))
    )
    (net (code "73") (name "VS2") (class "Default")
      (node (ref "Q5") (pin "3") (pinfunction "C_3") (pintype "passive"))
      (node (ref "R19") (pin "2") (pinfunction "2_2") (pintype "passive"))
      (node (ref "R20") (pin "1") (pinfunction "1_1") (pintype "passive"))
    )
    (net (code "74") (name "VS3") (class "Default")
      (node (ref "Q7") (pin "3") (pinfunction "C_3") (pintype "passive"))
      (node (ref "R24") (pin "2") (pinfunction "2_2") (pintype "passive"))
      (node (ref "R25") (pin "1") (pinfunction "1_1") (pintype "passive"))
    )
    (net (code "75") (name "VS4") (class "Default")
      (node (ref "Q1") (pin "3") (pinfunction "C_3") (pintype "passive"))
      (node (ref "R5") (pin "1") (pinfunction "1_1") (pintype "passive"))
      (node (ref "R7") (pin "2") (pinfunction "2_2") (pintype "passive"))
    )
    (net (code "76") (name "unconnected-(U$29-PA02{slash}EINT2{slash}AIN0{slash}Y0{slash}VOUT-Pad3)") (class "Default")
      (node (ref "U$29") (pin "3") (pinfunction "PA02/EINT2/AIN0/Y0/VOUT_3") (pintype "bidirectional"))
    )
    (net (code "77") (name "unconnected-(U$29-PA03{slash}EINT3{slash}VREFA{slash}AIN1-Pad4)") (class "Default")
      (node (ref "U$29") (pin "4") (pinfunction "PA03/EINT3/VREFA/AIN1_4") (pintype "bidirectional"))
    )
    (net (code "78") (name "unconnected-(U$29-PA08{slash}I2C{slash}AIN16{slash}SERCOM0+2.0{slash}I2SD1-Pad13)") (class "Default")
      (node (ref "U$29") (pin "13") (pinfunction "PA08/I2C/AIN16/SERCOM0+2.0/I2SD1_13") (pintype "bidirectional"))
    )
    (net (code "79") (name "unconnected-(U$29-PA09{slash}I2C{slash}I9{slash}AIN17{slash}SERCOM0+2.1{slash}I2SMC-Pad14)") (class "Default")
      (node (ref "U$29") (pin "14") (pinfunction "PA09/I2C/I9/AIN17/SERCOM0+2.1/I2SMC_14") (pintype "bidirectional"))
    )
    (net (code "80") (name "unconnected-(U$29-PA13{slash}I13{slash}I2C{slash}SERCOM2+4.1-Pad22)") (class "Default")
      (node (ref "U$29") (pin "22") (pinfunction "PA13/I13/I2C/SERCOM2+4.1_22") (pintype "bidirectional"))
    )
    (net (code "81") (name "unconnected-(U$29-PA19{slash}I3{slash}SERCOM1+3.3{slash}I2SD0-Pad28)") (class "Default")
      (node (ref "U$29") (pin "28") (pinfunction "PA19/I3/SERCOM1+3.3/I2SD0_28") (pintype "bidirectional"))
    )
    (net (code "82") (name "unconnected-(U$29-PA22{slash}I2C{slash}I6{slash}SERCOM3+5.0-Pad31)") (class "Default")
      (node (ref "U$29") (pin "31") (pinfunction "PA22/I2C/I6/SERCOM3+5.0_31") (pintype "bidirectional"))
    )
    (net (code "83") (name "unconnected-(U$29-PA23{slash}I2C{slash}I7{slash}SERCOM3+5.1{slash}SOF-Pad32)") (class "Default")
      (node (ref "U$29") (pin "32") (pinfunction "PA23/I2C/I7/SERCOM3+5.1/SOF_32") (pintype "bidirectional"))
    )
    (net (code "84") (name "unconnected-(U$29-PA27{slash}I15-Pad39)") (class "Default")
      (node (ref "U$29") (pin "39") (pinfunction "PA27/I15_39") (pintype "bidirectional"))
    )
    (net (code "85") (name "unconnected-(U$29-PA28{slash}I8-Pad41)") (class "Default")
      (node (ref "U$29") (pin "41") (pinfunction "PA28/I8_41") (pintype "bidirectional"))
    )
    (net (code "86") (name "unconnected-(U$29-PB03{slash}I3{slash}AIN11{slash}SERCOM5.1-Pad48)") (class "Default")
      (node (ref "U$29") (pin "48") (pinfunction "PB03/I3/AIN11/SERCOM5.1_48") (pintype "bidirectional"))
    )
    (net (code "87") (name "unconnected-(U$29-PB22{slash}I6{slash}SERCOM5.2-Pad37)") (class "Default")
      (node (ref "U$29") (pin "37") (pinfunction "PB22/I6/SERCOM5.2_37") (pintype "bidirectional"))
    )
    (net (code "88") (name "unconnected-(U1-NC-Pad4)") (class "Default")
      (node (ref "U1") (pin "4") (pinfunction "NC_4") (pintype "no_connect"))
    )
    (net (code "89") (name "unconnected-(U2-SPLIT-Pad5)") (class "Default")
      (node (ref "U2") (pin "5") (pinfunction "SPLIT_5") (pintype "bidirectional"))
    )
    (net (code "90") (name "unconnected-(U3-CLKOUT{slash}SOF-Pad1)") (class "Default")
      (node (ref "U3") (pin "1") (pinfunction "CLKOUT/SOF_1") (pintype "bidirectional"))
    )
    (net (code "91") (name "unconnected-(U3-~{RX0BF}-Pad10)") (class "Default")
      (node (ref "U3") (pin "10") (pinfunction "~{RX0BF}_10") (pintype "bidirectional"))
    )
    (net (code "92") (name "unconnected-(U3-~{RX1BF}-Pad9)") (class "Default")
      (node (ref "U3") (pin "9") (pinfunction "~{RX1BF}_9") (pintype "bidirectional"))
    )
  )
)
